# keyer.net
KiCad netlist of a schematic drawn in EAGLE
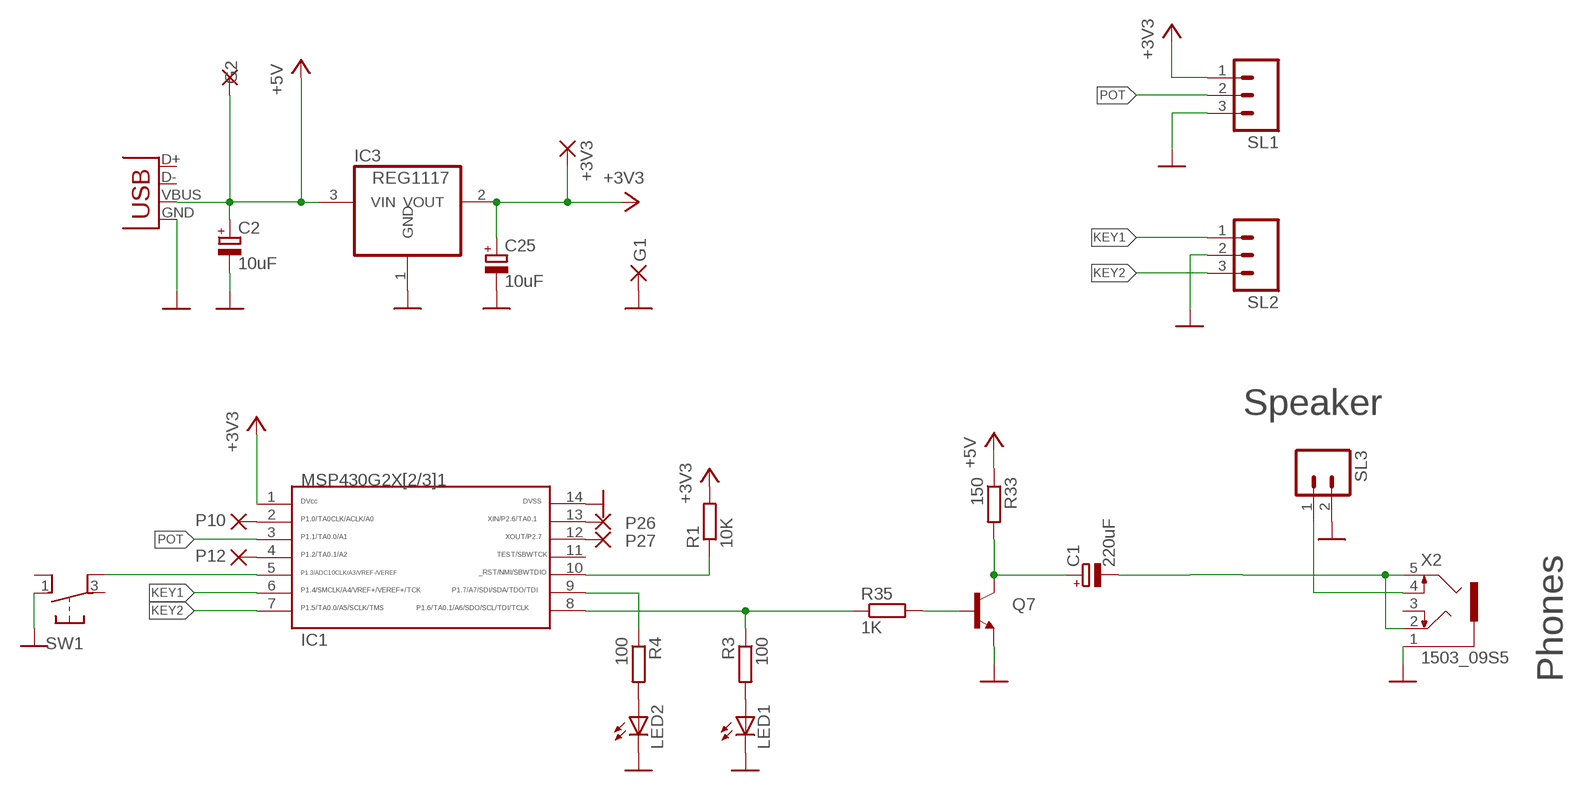
[diagram p0: schematic, sheet 1]

(export (version "E")
  (design (tool "Eeschema 10.0.6"))
  (components
    (comp (ref "+3V3")
      (value "1,6/0,8")
      (footprint "eagle-import:1,6_0,8")
      (libsource (lib "eagle-import") (part "1,6/0,8"))
    )
    (comp (ref "100")
      (value "R3")
      (footprint "eagle-import:R0805-SVO")
      (libsource (lib "eagle-import") (part "R-EU_R0805S"))
    )
    (comp (ref "C1")
      (value "220uF")
      (footprint "eagle-import:D_7343-31R")
      (libsource (lib "eagle-import") (part "CPOL-EUD/7343-31R"))
    )
    (comp (ref "C2")
      (value "10uF")
      (footprint "eagle-import:SMC_B")
      (libsource (lib "eagle-import") (part "CPOL-EUSMCB"))
    )
    (comp (ref "C25")
      (value "10uF")
      (footprint "eagle-import:SMC_B")
      (libsource (lib "eagle-import") (part "CPOL-EUSMCB"))
    )
    (comp (ref "G1")
      (value "1,6/0,8")
      (footprint "eagle-import:1,6_0,8")
      (libsource (lib "eagle-import") (part "1,6/0,8"))
    )
    (comp (ref "G2")
      (value "1,6/0,8")
      (footprint "eagle-import:1,6_0,8")
      (libsource (lib "eagle-import") (part "1,6/0,8"))
    )
    (comp (ref "IC1")
      (value "G2X[2/3]1---N14")
      (footprint "eagle-import:N14")
      (libsource (lib "eagle-import") (part "G2X[2/3]1---N14"))
    )
    (comp (ref "IC3")
      (value "REG1117")
      (footprint "eagle-import:SOT223")
      (libsource (lib "eagle-import") (part "REG1117"))
    )
    (comp (ref "LED1")
      (value "LED3MM")
      (footprint "eagle-import:LED3MM")
      (libsource (lib "eagle-import") (part "LED3MM"))
    )
    (comp (ref "LED2")
      (value "LED3MM")
      (footprint "eagle-import:LED3MM")
      (libsource (lib "eagle-import") (part "LED3MM"))
    )
    (comp (ref "P10")
      (value "1,6/0,8")
      (footprint "eagle-import:1,6_0,8")
      (libsource (lib "eagle-import") (part "1,6/0,8"))
    )
    (comp (ref "P12")
      (value "1,6/0,8")
      (footprint "eagle-import:1,6_0,8")
      (libsource (lib "eagle-import") (part "1,6/0,8"))
    )
    (comp (ref "P26")
      (value "1,6/0,8")
      (footprint "eagle-import:1,6_0,8")
      (libsource (lib "eagle-import") (part "1,6/0,8"))
    )
    (comp (ref "P27")
      (value "1,6/0,8")
      (footprint "eagle-import:1,6_0,8")
      (libsource (lib "eagle-import") (part "1,6/0,8"))
    )
    (comp (ref "Q7")
      (value "TRANSISTOR_NPNSOT23-3")
      (footprint "eagle-import:SOT23-3")
      (libsource (lib "eagle-import") (part "TRANSISTOR_NPNSOT23-3"))
    )
    (comp (ref "R1")
      (value "10K")
      (footprint "eagle-import:R0805-SVO")
      (libsource (lib "eagle-import") (part "R-EU_R0805S"))
    )
    (comp (ref "R4")
      (value "100")
      (footprint "eagle-import:R0805-SVO")
      (libsource (lib "eagle-import") (part "R-EU_R0805S"))
    )
    (comp (ref "R33")
      (value "150")
      (footprint "eagle-import:R0805-SVO")
      (libsource (lib "eagle-import") (part "R-EU_R0805S"))
    )
    (comp (ref "R35")
      (value "1K")
      (footprint "eagle-import:R0805-SVO")
      (libsource (lib "eagle-import") (part "R-EU_R0805S"))
    )
    (comp (ref "SL1")
      (value "M03")
      (footprint "eagle-import:03P")
      (libsource (lib "eagle-import") (part "M03"))
    )
    (comp (ref "SL2")
      (value "M03")
      (footprint "eagle-import:03P")
      (libsource (lib "eagle-import") (part "M03"))
    )
    (comp (ref "SL3")
      (value "M02")
      (footprint "eagle-import:02P")
      (libsource (lib "eagle-import") (part "M02"))
    )
    (comp (ref "SW1")
      (value "BUTTON_6X6_THRU")
      (footprint "eagle-import:6X6_BUTTON_THRU")
      (libsource (lib "eagle-import") (part "BUTTON_6X6_THRU"))
    )
    (comp (ref "X1")
      (value "USB-MICROB")
      (footprint "eagle-import:USB-MICROB")
      (libsource (lib "eagle-import") (part "USB-MICROB"))
    )
    (comp (ref "X2")
      (value "1503_09S5")
      (footprint "eagle-import:SYMMETRON5")
      (libsource (lib "eagle-import") (part "1503_09S5"))
    )
  )
  (nets
    (net (code "1") (name "+3V3") (class "Default")
      (node (ref "+3V3") (pin "1") (pinfunction "P_1") (pintype "passive"))
      (node (ref "C25") (pin "+") (pinfunction "+_+") (pintype "passive"))
      (node (ref "IC1") (pin "1") (pinfunction "1_1") (pintype "bidirectional"))
      (node (ref "IC3") (pin "2") (pinfunction "VOUT_2") (pintype "output"))
      (node (ref "R1") (pin "2") (pinfunction "2_2") (pintype "passive"))
      (node (ref "SL1") (pin "1") (pinfunction "1_1") (pintype "passive"))
    )
    (net (code "2") (name "+5V") (class "Default")
      (node (ref "C2") (pin "+") (pinfunction "+_+") (pintype "passive"))
      (node (ref "G2") (pin "1") (pinfunction "P_1") (pintype "passive"))
      (node (ref "IC3") (pin "3") (pinfunction "VIN_3") (pintype "input"))
      (node (ref "R33") (pin "1") (pinfunction "1_1") (pintype "passive"))
      (node (ref "X1") (pin "VBUS") (pinfunction "VBUS_VBUS") (pintype "bidirectional"))
    )
    (net (code "3") (name "GND") (class "Default")
      (node (ref "C2") (pin "-") (pinfunction "-_-") (pintype "passive"))
      (node (ref "C25") (pin "-") (pinfunction "-_-") (pintype "passive"))
      (node (ref "G1") (pin "1") (pinfunction "P_1") (pintype "passive"))
      (node (ref "IC1") (pin "14") (pinfunction "14_14") (pintype "bidirectional"))
      (node (ref "IC3") (pin "1") (pinfunction "GND_1") (pintype "power_in"))
      (node (ref "LED1") (pin "K") (pinfunction "C_K") (pintype "passive"))
      (node (ref "LED2") (pin "K") (pinfunction "C_K") (pintype "passive"))
      (node (ref "Q7") (pin "2") (pinfunction "E_2") (pintype "passive"))
      (node (ref "SL1") (pin "3") (pinfunction "3_3") (pintype "passive"))
      (node (ref "SL2") (pin "2") (pinfunction "2_2") (pintype "passive"))
      (node (ref "SL3") (pin "2") (pinfunction "2_2") (pintype "passive"))
      (node (ref "SW1") (pin "1") (pinfunction "P2_1") (pintype "passive"))
      (node (ref "X1") (pin "GND") (pinfunction "GND_GND") (pintype "bidirectional"))
      (node (ref "X2") (pin "1") (pinfunction "1_1") (pintype "passive"))
    )
    (net (code "4") (name "KEY1") (class "Default")
      (node (ref "IC1") (pin "6") (pinfunction "6_6") (pintype "bidirectional"))
      (node (ref "SL2") (pin "1") (pinfunction "1_1") (pintype "passive"))
    )
    (net (code "5") (name "KEY2") (class "Default")
      (node (ref "IC1") (pin "7") (pinfunction "7_7") (pintype "bidirectional"))
      (node (ref "SL2") (pin "3") (pinfunction "3_3") (pintype "passive"))
    )
    (net (code "6") (name "Net-(100-Pad1)") (class "Default")
      (node (ref "100") (pin "1") (pinfunction "1_1") (pintype "passive"))
      (node (ref "IC1") (pin "8") (pinfunction "8_8") (pintype "bidirectional"))
      (node (ref "R35") (pin "1") (pinfunction "1_1") (pintype "passive"))
    )
    (net (code "7") (name "Net-(100-Pad2)") (class "Default")
      (node (ref "100") (pin "2") (pinfunction "2_2") (pintype "passive"))
      (node (ref "LED1") (pin "A") (pinfunction "A_A") (pintype "passive"))
    )
    (net (code "8") (name "Net-(IC1-Pad5)") (class "Default")
      (node (ref "IC1") (pin "5") (pinfunction "5_5") (pintype "bidirectional"))
      (node (ref "SW1") (pin "4") (pinfunction "P1_4") (pintype "passive"))
    )
    (net (code "9") (name "Net-(IC1-Pad9)") (class "Default")
      (node (ref "IC1") (pin "9") (pinfunction "9_9") (pintype "bidirectional"))
      (node (ref "R4") (pin "1") (pinfunction "1_1") (pintype "passive"))
    )
    (net (code "10") (name "Net-(IC1-Pad10)") (class "Default")
      (node (ref "IC1") (pin "10") (pinfunction "10_10") (pintype "bidirectional"))
      (node (ref "R1") (pin "1") (pinfunction "1_1") (pintype "passive"))
    )
    (net (code "11") (name "Net-(LED2-PadA)") (class "Default")
      (node (ref "LED2") (pin "A") (pinfunction "A_A") (pintype "passive"))
      (node (ref "R4") (pin "2") (pinfunction "2_2") (pintype "passive"))
    )
    (net (code "12") (name "Net-(P10-P)") (class "Default")
      (node (ref "IC1") (pin "2") (pinfunction "2_2") (pintype "bidirectional"))
      (node (ref "P10") (pin "1") (pinfunction "P_1") (pintype "passive"))
    )
    (net (code "13") (name "Net-(P12-P)") (class "Default")
      (node (ref "IC1") (pin "4") (pinfunction "4_4") (pintype "bidirectional"))
      (node (ref "P12") (pin "1") (pinfunction "P_1") (pintype "passive"))
    )
    (net (code "14") (name "Net-(P26-P)") (class "Default")
      (node (ref "IC1") (pin "13") (pinfunction "13_13") (pintype "bidirectional"))
      (node (ref "P26") (pin "1") (pinfunction "P_1") (pintype "passive"))
    )
    (net (code "15") (name "Net-(P27-P)") (class "Default")
      (node (ref "IC1") (pin "12") (pinfunction "12_12") (pintype "bidirectional"))
      (node (ref "P27") (pin "1") (pinfunction "P_1") (pintype "passive"))
    )
    (net (code "16") (name "Net-(Q7-B)") (class "Default")
      (node (ref "Q7") (pin "1") (pinfunction "B_1") (pintype "passive"))
      (node (ref "R35") (pin "2") (pinfunction "2_2") (pintype "passive"))
    )
    (net (code "17") (name "Net-(Q7-C)") (class "Default")
      (node (ref "C1") (pin "+") (pinfunction "+_+") (pintype "passive"))
      (node (ref "Q7") (pin "3") (pinfunction "C_3") (pintype "passive"))
      (node (ref "R33") (pin "2") (pinfunction "2_2") (pintype "passive"))
    )
    (net (code "18") (name "Net-(X2-3)") (class "Default")
      (node (ref "C1") (pin "-") (pinfunction "-_-") (pintype "passive"))
      (node (ref "X2") (pin "2") (pinfunction "2_2") (pintype "passive"))
      (node (ref "X2") (pin "5") (pinfunction "3_5") (pintype "passive"))
    )
    (net (code "19") (name "Net-(X2-5)") (class "Default")
      (node (ref "SL3") (pin "1") (pinfunction "1_1") (pintype "passive"))
      (node (ref "X2") (pin "4") (pinfunction "5_4") (pintype "passive"))
    )
    (net (code "20") (name "POT") (class "Default")
      (node (ref "IC1") (pin "3") (pinfunction "3_3") (pintype "bidirectional"))
      (node (ref "SL1") (pin "2") (pinfunction "2_2") (pintype "passive"))
    )
    (net (code "21") (name "unconnected-(IC1-Pad11)") (class "Default")
      (node (ref "IC1") (pin "11") (pinfunction "11_11") (pintype "bidirectional"))
    )
    (net (code "22") (name "unconnected-(SW1-P1-Pad3)") (class "Default")
      (node (ref "SW1") (pin "3") (pinfunction "P1_3") (pintype "passive"))
    )
    (net (code "23") (name "unconnected-(SW1-P2-Pad2)") (class "Default")
      (node (ref "SW1") (pin "2") (pinfunction "P2_2") (pintype "passive"))
    )
    (net (code "24") (name "unconnected-(X1-PadD+)") (class "Default")
      (node (ref "X1") (pin "D+") (pinfunction "D+_D+") (pintype "bidirectional"))
    )
    (net (code "25") (name "unconnected-(X1-PadD-)") (class "Default")
      (node (ref "X1") (pin "D-") (pinfunction "D-_D-") (pintype "bidirectional"))
    )
    (net (code "26") (name "unconnected-(X2-4-Pad3)") (class "Default")
      (node (ref "X2") (pin "3") (pinfunction "4_3") (pintype "passive"))
    )
  )
)
